# Atari_AV-Adapter.net
KiCad netlist of a schematic drawn in EAGLE
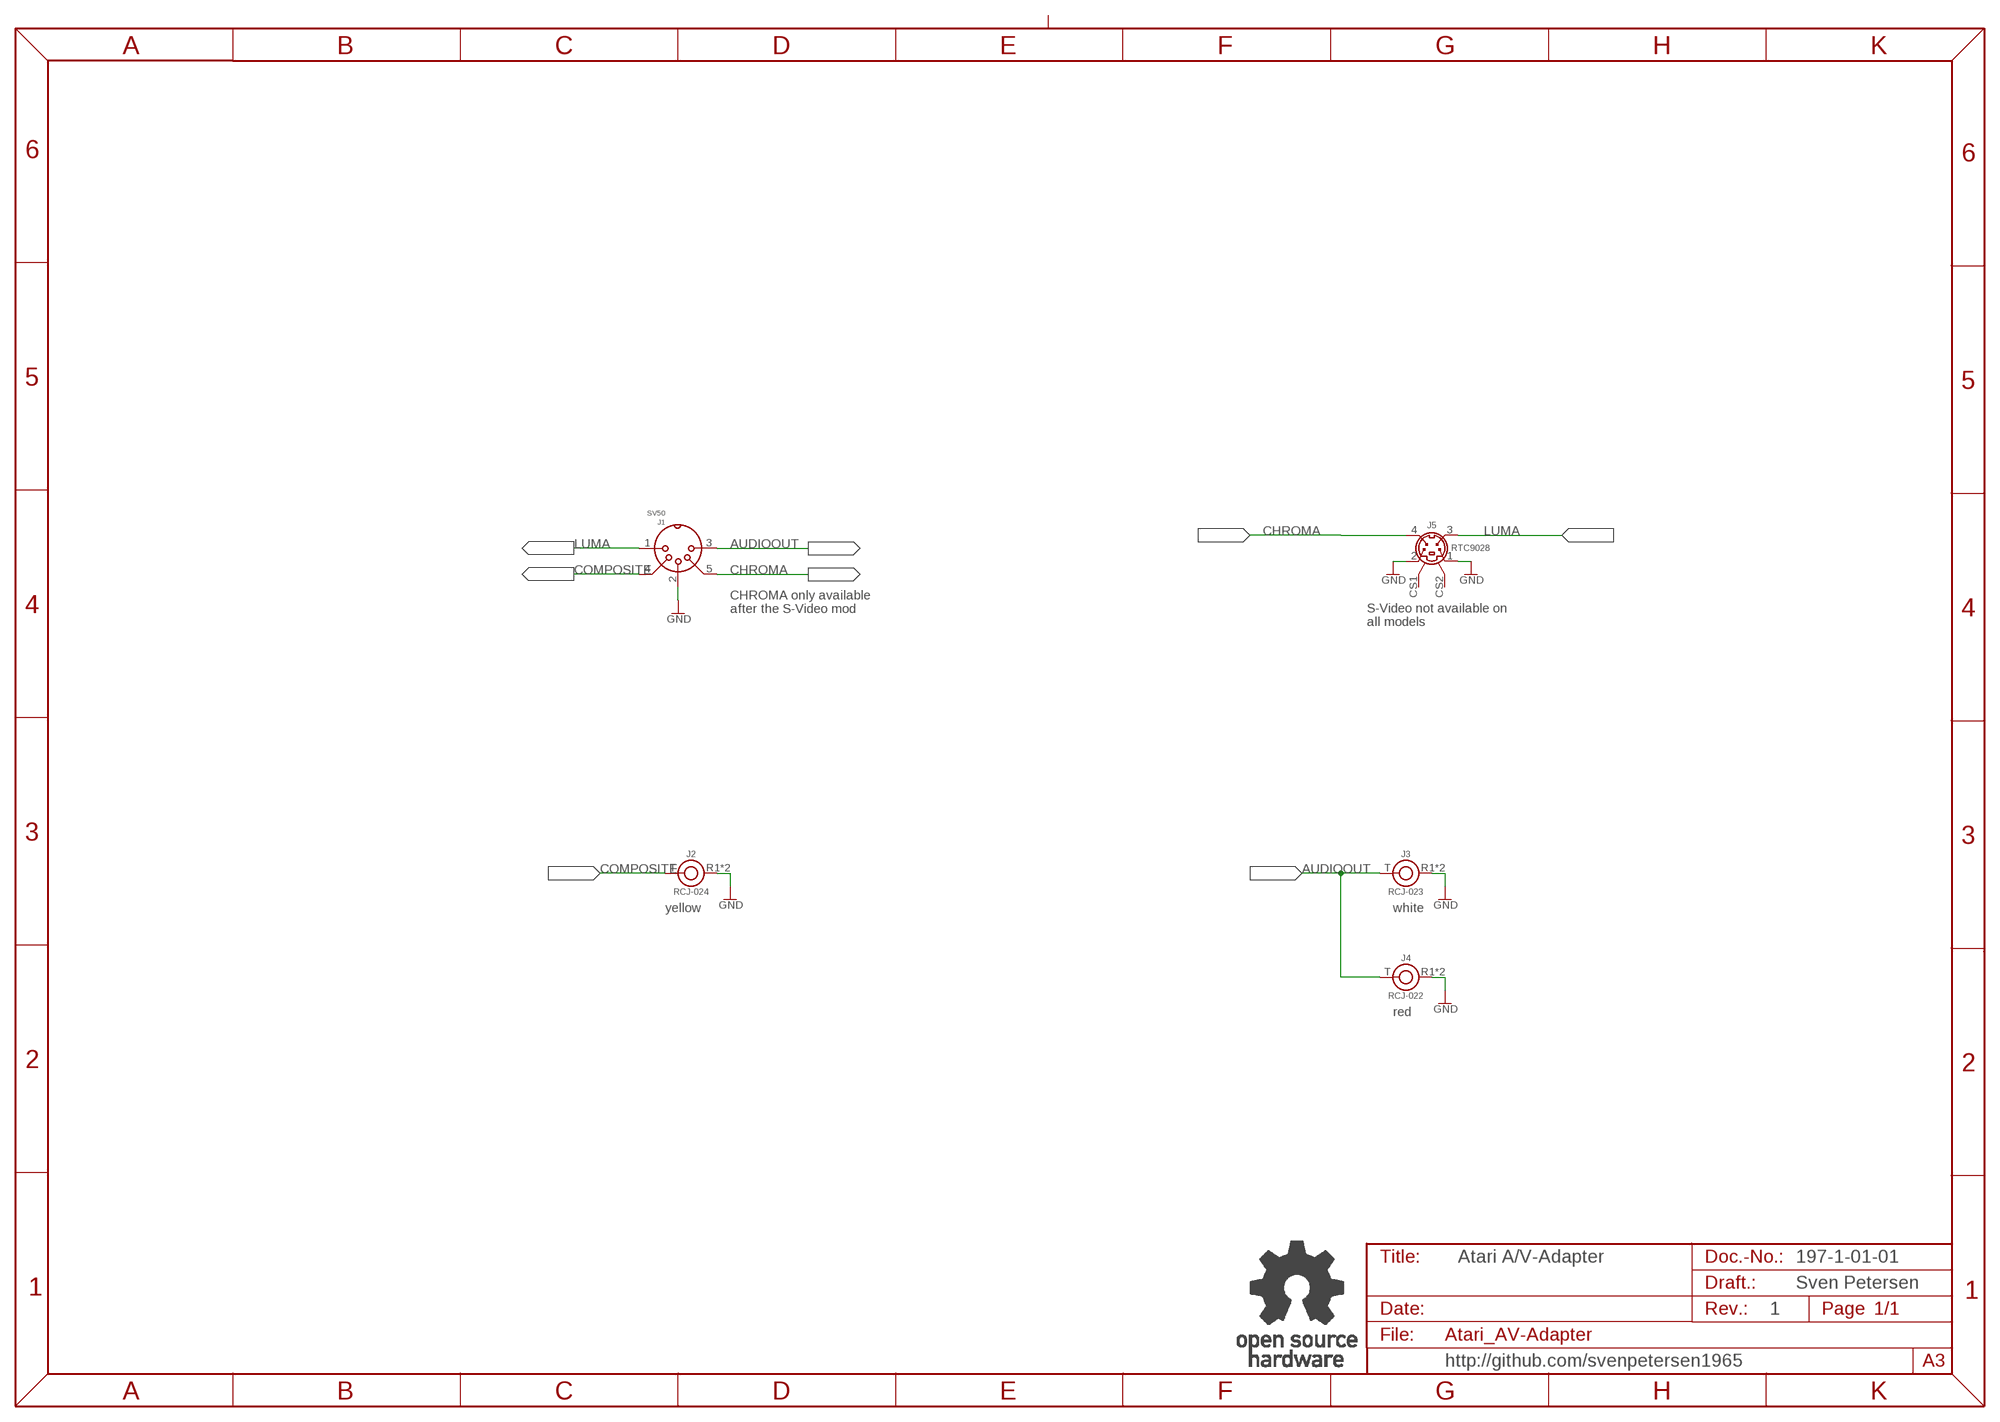
[diagram p0: schematic, sheet 1]

(export (version "E")
  (design (tool "Eeschema 10.0.6"))
  (components
    (comp (ref "J1")
      (value "SV50")
      (footprint "eagle-import:SV50_INNER")
      (libsource (lib "eagle-import") (part "SV50"))
    )
    (comp (ref "J2")
      (value "RCJ-024")
      (footprint "eagle-import:RCJ-02X")
      (libsource (lib "eagle-import") (part "RCJ-02X"))
    )
    (comp (ref "J3")
      (value "RCJ-023")
      (footprint "eagle-import:RCJ-02X")
      (libsource (lib "eagle-import") (part "RCJ-02X"))
    )
    (comp (ref "J4")
      (value "RCJ-022")
      (footprint "eagle-import:RCJ-02X")
      (libsource (lib "eagle-import") (part "RCJ-02X"))
    )
    (comp (ref "J5")
      (value "RTC9028")
      (footprint "eagle-import:MINIDIN4_V")
      (libsource (lib "eagle-import") (part "RTC9028"))
    )
    (comp (ref "U$25")
      (value "OPEN_SOURCE_HW")
      (footprint "eagle-import:OPENHW")
      (libsource (lib "eagle-import") (part "OPEN_SOURCE_HW"))
    )
  )
  (nets
    (net (code "1") (name "/AUDIOOUT") (class "Default")
      (node (ref "J1") (pin "3") (pinfunction "3_3") (pintype "bidirectional"))
      (node (ref "J3") (pin "T") (pinfunction "T_T") (pintype "bidirectional"))
      (node (ref "J4") (pin "T") (pinfunction "T_T") (pintype "bidirectional"))
    )
    (net (code "2") (name "/CHROMA") (class "Default")
      (node (ref "J1") (pin "5") (pinfunction "5_5") (pintype "bidirectional"))
      (node (ref "J5") (pin "4") (pinfunction "4_4") (pintype "bidirectional"))
    )
    (net (code "3") (name "/COMPOSITE") (class "Default")
      (node (ref "J1") (pin "4") (pinfunction "4_4") (pintype "bidirectional"))
      (node (ref "J2") (pin "T") (pinfunction "T_T") (pintype "bidirectional"))
    )
    (net (code "4") (name "/LUMA") (class "Default")
      (node (ref "J1") (pin "1") (pinfunction "1_1") (pintype "bidirectional"))
      (node (ref "J5") (pin "3") (pinfunction "3_3") (pintype "bidirectional"))
    )
    (net (code "5") (name "GND") (class "Default")
      (node (ref "J1") (pin "2") (pinfunction "2_2") (pintype "bidirectional"))
      (node (ref "J2") (pin "R1") (pinfunction "R_R1") (pintype "bidirectional"))
      (node (ref "J2") (pin "R2") (pinfunction "R_R2") (pintype "bidirectional"))
      (node (ref "J3") (pin "R1") (pinfunction "R_R1") (pintype "bidirectional"))
      (node (ref "J3") (pin "R2") (pinfunction "R_R2") (pintype "bidirectional"))
      (node (ref "J4") (pin "R1") (pinfunction "R_R1") (pintype "bidirectional"))
      (node (ref "J4") (pin "R2") (pinfunction "R_R2") (pintype "bidirectional"))
      (node (ref "J5") (pin "1") (pinfunction "1_1") (pintype "bidirectional"))
      (node (ref "J5") (pin "2") (pinfunction "2_2") (pintype "bidirectional"))
    )
    (net (code "6") (name "unconnected-(J5-PadCS1)") (class "Default")
      (node (ref "J5") (pin "CS1") (pinfunction "CS1_CS1") (pintype "bidirectional"))
    )
    (net (code "7") (name "unconnected-(J5-PadCS2)") (class "Default")
      (node (ref "J5") (pin "CS2") (pinfunction "CS2_CS2") (pintype "bidirectional"))
    )
  )
)
